# Mainboard_MCU_Breakout.net
KiCad netlist of a schematic drawn in Altium Designer
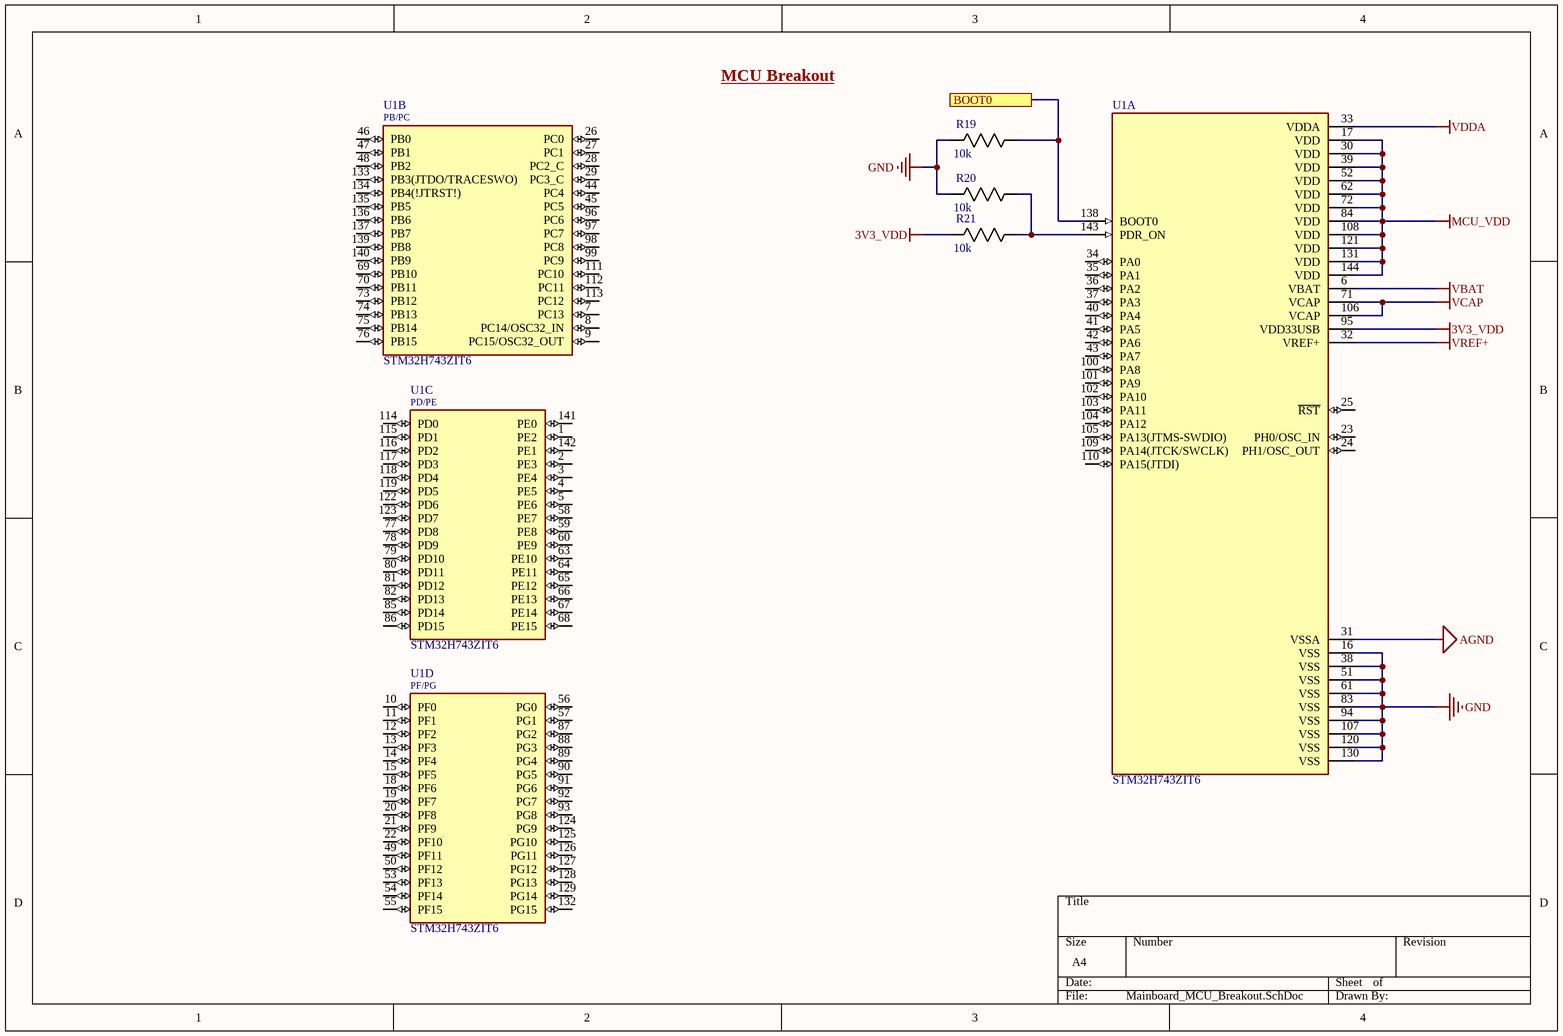
[diagram p0: Mainboard_MCU_Breakout.SchDoc]

(export (version "E")
  (design (tool "Eeschema 10.0.6"))
  (components
    (comp (ref "R19")
      (value "10k")
      (footprint "0805")
      (description "RES SMD 10K OHM 1% 1/8W 0805")
      (fields (field (name "TOLERANCE") "1%"))
      (libsource (lib "AltiumLibraries") (part "RES 10k 1/8W - 1%"))
    )
    (comp (ref "R20")
      (value "10k")
      (footprint "0805")
      (description "RES SMD 10K OHM 1% 1/8W 0805")
      (fields (field (name "TOLERANCE") "1%"))
      (libsource (lib "") (part "RES 10k 1/8W - 1%_1"))
    )
    (comp (ref "R21")
      (value "10k")
      (footprint "0805")
      (description "RES SMD 10K OHM 1% 1/8W 0805")
      (fields (field (name "TOLERANCE") "1%"))
      (libsource (lib "") (part "RES 10k 1/8W - 1%_1"))
    )
    (comp (ref "U1")
      (value "STM32H743ZIT6")
      (footprint "QFP50P2200X2200X160-144N")
      (description "ARM® Cortex®-M7 STM32H7 Microcontroller IC 32-Bit 480MHz 2MB (2M x 8) FLASH 144-LQFP (20x20)")
      (fields (field (name "MF") "STMicroelectronics"))
      (libsource (lib "AltiumLibraries") (part "STM32H743ZIT6"))
    )
  )
  (nets
    (net (code "1") (name "/BOOT0") (class "Default")
      (node (ref "R19") (pin "1") (pinfunction "R1_1") (pintype "passive"))
      (node (ref "U1") (pin "138") (pinfunction "BOOT0_138") (pintype "input"))
    )
    (net (code "2") (name "3V3_VDD") (class "Default")
      (node (ref "R21") (pin "2") (pinfunction "R2_2") (pintype "passive"))
      (node (ref "U1") (pin "95") (pinfunction "VDD33USB_95") (pintype "power_in"))
    )
    (net (code "3") (name "AGND") (class "Default")
      (node (ref "U1") (pin "31") (pinfunction "VSSA_31") (pintype "power_in"))
    )
    (net (code "4") (name "GND") (class "Default")
      (node (ref "R19") (pin "2") (pinfunction "R2_2") (pintype "passive"))
      (node (ref "R20") (pin "2") (pinfunction "R2_2") (pintype "passive"))
      (node (ref "U1") (pin "107") (pinfunction "VSS_107") (pintype "power_in"))
      (node (ref "U1") (pin "120") (pinfunction "VSS_120") (pintype "power_in"))
      (node (ref "U1") (pin "130") (pinfunction "VSS_130") (pintype "power_in"))
      (node (ref "U1") (pin "16") (pinfunction "VSS_16") (pintype "power_in"))
      (node (ref "U1") (pin "38") (pinfunction "VSS_38") (pintype "power_in"))
      (node (ref "U1") (pin "51") (pinfunction "VSS_51") (pintype "power_in"))
      (node (ref "U1") (pin "61") (pinfunction "VSS_61") (pintype "power_in"))
      (node (ref "U1") (pin "83") (pinfunction "VSS_83") (pintype "power_in"))
      (node (ref "U1") (pin "94") (pinfunction "VSS_94") (pintype "power_in"))
    )
    (net (code "5") (name "MCU_VDD") (class "Default")
      (node (ref "U1") (pin "108") (pinfunction "VDD_108") (pintype "power_in"))
      (node (ref "U1") (pin "121") (pinfunction "VDD_121") (pintype "power_in"))
      (node (ref "U1") (pin "131") (pinfunction "VDD_131") (pintype "power_in"))
      (node (ref "U1") (pin "144") (pinfunction "VDD_144") (pintype "power_in"))
      (node (ref "U1") (pin "17") (pinfunction "VDD_17") (pintype "power_in"))
      (node (ref "U1") (pin "30") (pinfunction "VDD_30") (pintype "power_in"))
      (node (ref "U1") (pin "39") (pinfunction "VDD_39") (pintype "power_in"))
      (node (ref "U1") (pin "52") (pinfunction "VDD_52") (pintype "power_in"))
      (node (ref "U1") (pin "62") (pinfunction "VDD_62") (pintype "power_in"))
      (node (ref "U1") (pin "72") (pinfunction "VDD_72") (pintype "power_in"))
      (node (ref "U1") (pin "84") (pinfunction "VDD_84") (pintype "power_in"))
    )
    (net (code "6") (name "Net-(R20-R1)") (class "Default")
      (node (ref "R20") (pin "1") (pinfunction "R1_1") (pintype "passive"))
      (node (ref "R21") (pin "1") (pinfunction "R1_1") (pintype "passive"))
      (node (ref "U1") (pin "143") (pinfunction "PDR_ON_143") (pintype "input"))
    )
    (net (code "7") (name "VBAT") (class "Default")
      (node (ref "U1") (pin "6") (pinfunction "VBAT_6") (pintype "power_in"))
    )
    (net (code "8") (name "VCAP") (class "Default")
      (node (ref "U1") (pin "106") (pinfunction "VCAP_106") (pintype "power_in"))
      (node (ref "U1") (pin "71") (pinfunction "VCAP_71") (pintype "power_in"))
    )
    (net (code "9") (name "VDDA") (class "Default")
      (node (ref "U1") (pin "33") (pinfunction "VDDA_33") (pintype "power_in"))
    )
    (net (code "10") (name "VREF+") (class "Default")
      (node (ref "U1") (pin "32") (pinfunction "VREF+_32") (pintype "power_in"))
    )
    (net (code "11") (name "unconnected-(U1A-PA0-Pad34)") (class "Default")
      (node (ref "U1") (pin "34") (pinfunction "PA0_34") (pintype "bidirectional"))
    )
    (net (code "12") (name "unconnected-(U1A-PA1-Pad35)") (class "Default")
      (node (ref "U1") (pin "35") (pinfunction "PA1_35") (pintype "bidirectional"))
    )
    (net (code "13") (name "unconnected-(U1A-PA2-Pad36)") (class "Default")
      (node (ref "U1") (pin "36") (pinfunction "PA2_36") (pintype "bidirectional"))
    )
    (net (code "14") (name "unconnected-(U1A-PA3-Pad37)") (class "Default")
      (node (ref "U1") (pin "37") (pinfunction "PA3_37") (pintype "bidirectional"))
    )
    (net (code "15") (name "unconnected-(U1A-PA4-Pad40)") (class "Default")
      (node (ref "U1") (pin "40") (pinfunction "PA4_40") (pintype "bidirectional"))
    )
    (net (code "16") (name "unconnected-(U1A-PA5-Pad41)") (class "Default")
      (node (ref "U1") (pin "41") (pinfunction "PA5_41") (pintype "bidirectional"))
    )
    (net (code "17") (name "unconnected-(U1A-PA6-Pad42)") (class "Default")
      (node (ref "U1") (pin "42") (pinfunction "PA6_42") (pintype "bidirectional"))
    )
    (net (code "18") (name "unconnected-(U1A-PA7-Pad43)") (class "Default")
      (node (ref "U1") (pin "43") (pinfunction "PA7_43") (pintype "bidirectional"))
    )
    (net (code "19") (name "unconnected-(U1A-PA8-Pad100)") (class "Default")
      (node (ref "U1") (pin "100") (pinfunction "PA8_100") (pintype "bidirectional"))
    )
    (net (code "20") (name "unconnected-(U1A-PA9-Pad101)") (class "Default")
      (node (ref "U1") (pin "101") (pinfunction "PA9_101") (pintype "bidirectional"))
    )
    (net (code "21") (name "unconnected-(U1A-PA10-Pad102)") (class "Default")
      (node (ref "U1") (pin "102") (pinfunction "PA10_102") (pintype "bidirectional"))
    )
    (net (code "22") (name "unconnected-(U1A-PA11-Pad103)") (class "Default")
      (node (ref "U1") (pin "103") (pinfunction "PA11_103") (pintype "bidirectional"))
    )
    (net (code "23") (name "unconnected-(U1A-PA12-Pad104)") (class "Default")
      (node (ref "U1") (pin "104") (pinfunction "PA12_104") (pintype "bidirectional"))
    )
    (net (code "24") (name "unconnected-(U1A-PA13(JTMS-SWDIO)-Pad105)") (class "Default")
      (node (ref "U1") (pin "105") (pinfunction "PA13(JTMS-SWDIO)_105") (pintype "bidirectional"))
    )
    (net (code "25") (name "unconnected-(U1A-PA14(JTCK{slash}SWCLK)-Pad109)") (class "Default")
      (node (ref "U1") (pin "109") (pinfunction "PA14(JTCK/SWCLK)_109") (pintype "bidirectional"))
    )
    (net (code "26") (name "unconnected-(U1A-PA15(JTDI)-Pad110)") (class "Default")
      (node (ref "U1") (pin "110") (pinfunction "PA15(JTDI)_110") (pintype "bidirectional"))
    )
    (net (code "27") (name "unconnected-(U1A-PH0{slash}OSC_IN-Pad23)") (class "Default")
      (node (ref "U1") (pin "23") (pinfunction "PH0/OSC_IN_23") (pintype "bidirectional"))
    )
    (net (code "28") (name "unconnected-(U1A-PH1{slash}OSC_OUT-Pad24)") (class "Default")
      (node (ref "U1") (pin "24") (pinfunction "PH1/OSC_OUT_24") (pintype "bidirectional"))
    )
    (net (code "29") (name "unconnected-(U1A-~{RST}-Pad25)") (class "Default")
      (node (ref "U1") (pin "25") (pinfunction "~{RST}_25") (pintype "bidirectional"))
    )
    (net (code "30") (name "unconnected-(U1B-PB0-Pad46)") (class "Default")
      (node (ref "U1") (pin "46") (pinfunction "PB0_46") (pintype "bidirectional"))
    )
    (net (code "31") (name "unconnected-(U1B-PB1-Pad47)") (class "Default")
      (node (ref "U1") (pin "47") (pinfunction "PB1_47") (pintype "bidirectional"))
    )
    (net (code "32") (name "unconnected-(U1B-PB2-Pad48)") (class "Default")
      (node (ref "U1") (pin "48") (pinfunction "PB2_48") (pintype "bidirectional"))
    )
    (net (code "33") (name "unconnected-(U1B-PB3(JTDO{slash}TRACESWO)-Pad133)") (class "Default")
      (node (ref "U1") (pin "133") (pinfunction "PB3(JTDO/TRACESWO)_133") (pintype "bidirectional"))
    )
    (net (code "34") (name "unconnected-(U1B-PB4(!JTRST!)-Pad134)") (class "Default")
      (node (ref "U1") (pin "134") (pinfunction "PB4(!JTRST!)_134") (pintype "bidirectional"))
    )
    (net (code "35") (name "unconnected-(U1B-PB5-Pad135)") (class "Default")
      (node (ref "U1") (pin "135") (pinfunction "PB5_135") (pintype "bidirectional"))
    )
    (net (code "36") (name "unconnected-(U1B-PB6-Pad136)") (class "Default")
      (node (ref "U1") (pin "136") (pinfunction "PB6_136") (pintype "bidirectional"))
    )
    (net (code "37") (name "unconnected-(U1B-PB7-Pad137)") (class "Default")
      (node (ref "U1") (pin "137") (pinfunction "PB7_137") (pintype "bidirectional"))
    )
    (net (code "38") (name "unconnected-(U1B-PB8-Pad139)") (class "Default")
      (node (ref "U1") (pin "139") (pinfunction "PB8_139") (pintype "bidirectional"))
    )
    (net (code "39") (name "unconnected-(U1B-PB9-Pad140)") (class "Default")
      (node (ref "U1") (pin "140") (pinfunction "PB9_140") (pintype "bidirectional"))
    )
    (net (code "40") (name "unconnected-(U1B-PB10-Pad69)") (class "Default")
      (node (ref "U1") (pin "69") (pinfunction "PB10_69") (pintype "bidirectional"))
    )
    (net (code "41") (name "unconnected-(U1B-PB11-Pad70)") (class "Default")
      (node (ref "U1") (pin "70") (pinfunction "PB11_70") (pintype "bidirectional"))
    )
    (net (code "42") (name "unconnected-(U1B-PB12-Pad73)") (class "Default")
      (node (ref "U1") (pin "73") (pinfunction "PB12_73") (pintype "bidirectional"))
    )
    (net (code "43") (name "unconnected-(U1B-PB13-Pad74)") (class "Default")
      (node (ref "U1") (pin "74") (pinfunction "PB13_74") (pintype "bidirectional"))
    )
    (net (code "44") (name "unconnected-(U1B-PB14-Pad75)") (class "Default")
      (node (ref "U1") (pin "75") (pinfunction "PB14_75") (pintype "bidirectional"))
    )
    (net (code "45") (name "unconnected-(U1B-PB15-Pad76)") (class "Default")
      (node (ref "U1") (pin "76") (pinfunction "PB15_76") (pintype "bidirectional"))
    )
    (net (code "46") (name "unconnected-(U1B-PC0-Pad26)") (class "Default")
      (node (ref "U1") (pin "26") (pinfunction "PC0_26") (pintype "bidirectional"))
    )
    (net (code "47") (name "unconnected-(U1B-PC1-Pad27)") (class "Default")
      (node (ref "U1") (pin "27") (pinfunction "PC1_27") (pintype "bidirectional"))
    )
    (net (code "48") (name "unconnected-(U1B-PC2_C-Pad28)") (class "Default")
      (node (ref "U1") (pin "28") (pinfunction "PC2_C_28") (pintype "bidirectional"))
    )
    (net (code "49") (name "unconnected-(U1B-PC3_C-Pad29)") (class "Default")
      (node (ref "U1") (pin "29") (pinfunction "PC3_C_29") (pintype "bidirectional"))
    )
    (net (code "50") (name "unconnected-(U1B-PC4-Pad44)") (class "Default")
      (node (ref "U1") (pin "44") (pinfunction "PC4_44") (pintype "bidirectional"))
    )
    (net (code "51") (name "unconnected-(U1B-PC5-Pad45)") (class "Default")
      (node (ref "U1") (pin "45") (pinfunction "PC5_45") (pintype "bidirectional"))
    )
    (net (code "52") (name "unconnected-(U1B-PC6-Pad96)") (class "Default")
      (node (ref "U1") (pin "96") (pinfunction "PC6_96") (pintype "bidirectional"))
    )
    (net (code "53") (name "unconnected-(U1B-PC7-Pad97)") (class "Default")
      (node (ref "U1") (pin "97") (pinfunction "PC7_97") (pintype "bidirectional"))
    )
    (net (code "54") (name "unconnected-(U1B-PC8-Pad98)") (class "Default")
      (node (ref "U1") (pin "98") (pinfunction "PC8_98") (pintype "bidirectional"))
    )
    (net (code "55") (name "unconnected-(U1B-PC9-Pad99)") (class "Default")
      (node (ref "U1") (pin "99") (pinfunction "PC9_99") (pintype "bidirectional"))
    )
    (net (code "56") (name "unconnected-(U1B-PC10-Pad111)") (class "Default")
      (node (ref "U1") (pin "111") (pinfunction "PC10_111") (pintype "bidirectional"))
    )
    (net (code "57") (name "unconnected-(U1B-PC11-Pad112)") (class "Default")
      (node (ref "U1") (pin "112") (pinfunction "PC11_112") (pintype "bidirectional"))
    )
    (net (code "58") (name "unconnected-(U1B-PC12-Pad113)") (class "Default")
      (node (ref "U1") (pin "113") (pinfunction "PC12_113") (pintype "bidirectional"))
    )
    (net (code "59") (name "unconnected-(U1B-PC13-Pad7)") (class "Default")
      (node (ref "U1") (pin "7") (pinfunction "PC13_7") (pintype "bidirectional"))
    )
    (net (code "60") (name "unconnected-(U1B-PC14{slash}OSC32_IN-Pad8)") (class "Default")
      (node (ref "U1") (pin "8") (pinfunction "PC14/OSC32_IN_8") (pintype "bidirectional"))
    )
    (net (code "61") (name "unconnected-(U1B-PC15{slash}OSC32_OUT-Pad9)") (class "Default")
      (node (ref "U1") (pin "9") (pinfunction "PC15/OSC32_OUT_9") (pintype "bidirectional"))
    )
    (net (code "62") (name "unconnected-(U1C-PD0-Pad114)") (class "Default")
      (node (ref "U1") (pin "114") (pinfunction "PD0_114") (pintype "bidirectional"))
    )
    (net (code "63") (name "unconnected-(U1C-PD1-Pad115)") (class "Default")
      (node (ref "U1") (pin "115") (pinfunction "PD1_115") (pintype "bidirectional"))
    )
    (net (code "64") (name "unconnected-(U1C-PD2-Pad116)") (class "Default")
      (node (ref "U1") (pin "116") (pinfunction "PD2_116") (pintype "bidirectional"))
    )
    (net (code "65") (name "unconnected-(U1C-PD3-Pad117)") (class "Default")
      (node (ref "U1") (pin "117") (pinfunction "PD3_117") (pintype "bidirectional"))
    )
    (net (code "66") (name "unconnected-(U1C-PD4-Pad118)") (class "Default")
      (node (ref "U1") (pin "118") (pinfunction "PD4_118") (pintype "bidirectional"))
    )
    (net (code "67") (name "unconnected-(U1C-PD5-Pad119)") (class "Default")
      (node (ref "U1") (pin "119") (pinfunction "PD5_119") (pintype "bidirectional"))
    )
    (net (code "68") (name "unconnected-(U1C-PD6-Pad122)") (class "Default")
      (node (ref "U1") (pin "122") (pinfunction "PD6_122") (pintype "bidirectional"))
    )
    (net (code "69") (name "unconnected-(U1C-PD7-Pad123)") (class "Default")
      (node (ref "U1") (pin "123") (pinfunction "PD7_123") (pintype "bidirectional"))
    )
    (net (code "70") (name "unconnected-(U1C-PD8-Pad77)") (class "Default")
      (node (ref "U1") (pin "77") (pinfunction "PD8_77") (pintype "bidirectional"))
    )
    (net (code "71") (name "unconnected-(U1C-PD9-Pad78)") (class "Default")
      (node (ref "U1") (pin "78") (pinfunction "PD9_78") (pintype "bidirectional"))
    )
    (net (code "72") (name "unconnected-(U1C-PD10-Pad79)") (class "Default")
      (node (ref "U1") (pin "79") (pinfunction "PD10_79") (pintype "bidirectional"))
    )
    (net (code "73") (name "unconnected-(U1C-PD11-Pad80)") (class "Default")
      (node (ref "U1") (pin "80") (pinfunction "PD11_80") (pintype "bidirectional"))
    )
    (net (code "74") (name "unconnected-(U1C-PD12-Pad81)") (class "Default")
      (node (ref "U1") (pin "81") (pinfunction "PD12_81") (pintype "bidirectional"))
    )
    (net (code "75") (name "unconnected-(U1C-PD13-Pad82)") (class "Default")
      (node (ref "U1") (pin "82") (pinfunction "PD13_82") (pintype "bidirectional"))
    )
    (net (code "76") (name "unconnected-(U1C-PD14-Pad85)") (class "Default")
      (node (ref "U1") (pin "85") (pinfunction "PD14_85") (pintype "bidirectional"))
    )
    (net (code "77") (name "unconnected-(U1C-PD15-Pad86)") (class "Default")
      (node (ref "U1") (pin "86") (pinfunction "PD15_86") (pintype "bidirectional"))
    )
    (net (code "78") (name "unconnected-(U1C-PE0-Pad141)") (class "Default")
      (node (ref "U1") (pin "141") (pinfunction "PE0_141") (pintype "bidirectional"))
    )
    (net (code "79") (name "unconnected-(U1C-PE1-Pad142)") (class "Default")
      (node (ref "U1") (pin "142") (pinfunction "PE1_142") (pintype "bidirectional"))
    )
    (net (code "80") (name "unconnected-(U1C-PE2-Pad1)") (class "Default")
      (node (ref "U1") (pin "1") (pinfunction "PE2_1") (pintype "bidirectional"))
    )
    (net (code "81") (name "unconnected-(U1C-PE3-Pad2)") (class "Default")
      (node (ref "U1") (pin "2") (pinfunction "PE3_2") (pintype "bidirectional"))
    )
    (net (code "82") (name "unconnected-(U1C-PE4-Pad3)") (class "Default")
      (node (ref "U1") (pin "3") (pinfunction "PE4_3") (pintype "bidirectional"))
    )
    (net (code "83") (name "unconnected-(U1C-PE5-Pad4)") (class "Default")
      (node (ref "U1") (pin "4") (pinfunction "PE5_4") (pintype "bidirectional"))
    )
    (net (code "84") (name "unconnected-(U1C-PE6-Pad5)") (class "Default")
      (node (ref "U1") (pin "5") (pinfunction "PE6_5") (pintype "bidirectional"))
    )
    (net (code "85") (name "unconnected-(U1C-PE7-Pad58)") (class "Default")
      (node (ref "U1") (pin "58") (pinfunction "PE7_58") (pintype "bidirectional"))
    )
    (net (code "86") (name "unconnected-(U1C-PE8-Pad59)") (class "Default")
      (node (ref "U1") (pin "59") (pinfunction "PE8_59") (pintype "bidirectional"))
    )
    (net (code "87") (name "unconnected-(U1C-PE9-Pad60)") (class "Default")
      (node (ref "U1") (pin "60") (pinfunction "PE9_60") (pintype "bidirectional"))
    )
    (net (code "88") (name "unconnected-(U1C-PE10-Pad63)") (class "Default")
      (node (ref "U1") (pin "63") (pinfunction "PE10_63") (pintype "bidirectional"))
    )
    (net (code "89") (name "unconnected-(U1C-PE11-Pad64)") (class "Default")
      (node (ref "U1") (pin "64") (pinfunction "PE11_64") (pintype "bidirectional"))
    )
    (net (code "90") (name "unconnected-(U1C-PE12-Pad65)") (class "Default")
      (node (ref "U1") (pin "65") (pinfunction "PE12_65") (pintype "bidirectional"))
    )
    (net (code "91") (name "unconnected-(U1C-PE13-Pad66)") (class "Default")
      (node (ref "U1") (pin "66") (pinfunction "PE13_66") (pintype "bidirectional"))
    )
    (net (code "92") (name "unconnected-(U1C-PE14-Pad67)") (class "Default")
      (node (ref "U1") (pin "67") (pinfunction "PE14_67") (pintype "bidirectional"))
    )
    (net (code "93") (name "unconnected-(U1C-PE15-Pad68)") (class "Default")
      (node (ref "U1") (pin "68") (pinfunction "PE15_68") (pintype "bidirectional"))
    )
    (net (code "94") (name "unconnected-(U1D-PF0-Pad10)") (class "Default")
      (node (ref "U1") (pin "10") (pinfunction "PF0_10") (pintype "bidirectional"))
    )
    (net (code "95") (name "unconnected-(U1D-PF1-Pad11)") (class "Default")
      (node (ref "U1") (pin "11") (pinfunction "PF1_11") (pintype "bidirectional"))
    )
    (net (code "96") (name "unconnected-(U1D-PF2-Pad12)") (class "Default")
      (node (ref "U1") (pin "12") (pinfunction "PF2_12") (pintype "bidirectional"))
    )
    (net (code "97") (name "unconnected-(U1D-PF3-Pad13)") (class "Default")
      (node (ref "U1") (pin "13") (pinfunction "PF3_13") (pintype "bidirectional"))
    )
    (net (code "98") (name "unconnected-(U1D-PF4-Pad14)") (class "Default")
      (node (ref "U1") (pin "14") (pinfunction "PF4_14") (pintype "bidirectional"))
    )
    (net (code "99") (name "unconnected-(U1D-PF5-Pad15)") (class "Default")
      (node (ref "U1") (pin "15") (pinfunction "PF5_15") (pintype "bidirectional"))
    )
    (net (code "100") (name "unconnected-(U1D-PF6-Pad18)") (class "Default")
      (node (ref "U1") (pin "18") (pinfunction "PF6_18") (pintype "bidirectional"))
    )
    (net (code "101") (name "unconnected-(U1D-PF7-Pad19)") (class "Default")
      (node (ref "U1") (pin "19") (pinfunction "PF7_19") (pintype "bidirectional"))
    )
    (net (code "102") (name "unconnected-(U1D-PF8-Pad20)") (class "Default")
      (node (ref "U1") (pin "20") (pinfunction "PF8_20") (pintype "bidirectional"))
    )
    (net (code "103") (name "unconnected-(U1D-PF9-Pad21)") (class "Default")
      (node (ref "U1") (pin "21") (pinfunction "PF9_21") (pintype "bidirectional"))
    )
    (net (code "104") (name "unconnected-(U1D-PF10-Pad22)") (class "Default")
      (node (ref "U1") (pin "22") (pinfunction "PF10_22") (pintype "bidirectional"))
    )
    (net (code "105") (name "unconnected-(U1D-PF11-Pad49)") (class "Default")
      (node (ref "U1") (pin "49") (pinfunction "PF11_49") (pintype "bidirectional"))
    )
    (net (code "106") (name "unconnected-(U1D-PF12-Pad50)") (class "Default")
      (node (ref "U1") (pin "50") (pinfunction "PF12_50") (pintype "bidirectional"))
    )
    (net (code "107") (name "unconnected-(U1D-PF13-Pad53)") (class "Default")
      (node (ref "U1") (pin "53") (pinfunction "PF13_53") (pintype "bidirectional"))
    )
    (net (code "108") (name "unconnected-(U1D-PF14-Pad54)") (class "Default")
      (node (ref "U1") (pin "54") (pinfunction "PF14_54") (pintype "bidirectional"))
    )
    (net (code "109") (name "unconnected-(U1D-PF15-Pad55)") (class "Default")
      (node (ref "U1") (pin "55") (pinfunction "PF15_55") (pintype "bidirectional"))
    )
    (net (code "110") (name "unconnected-(U1D-PG0-Pad56)") (class "Default")
      (node (ref "U1") (pin "56") (pinfunction "PG0_56") (pintype "bidirectional"))
    )
    (net (code "111") (name "unconnected-(U1D-PG1-Pad57)") (class "Default")
      (node (ref "U1") (pin "57") (pinfunction "PG1_57") (pintype "bidirectional"))
    )
    (net (code "112") (name "unconnected-(U1D-PG2-Pad87)") (class "Default")
      (node (ref "U1") (pin "87") (pinfunction "PG2_87") (pintype "bidirectional"))
    )
    (net (code "113") (name "unconnected-(U1D-PG3-Pad88)") (class "Default")
      (node (ref "U1") (pin "88") (pinfunction "PG3_88") (pintype "bidirectional"))
    )
    (net (code "114") (name "unconnected-(U1D-PG4-Pad89)") (class "Default")
      (node (ref "U1") (pin "89") (pinfunction "PG4_89") (pintype "bidirectional"))
    )
    (net (code "115") (name "unconnected-(U1D-PG5-Pad90)") (class "Default")
      (node (ref "U1") (pin "90") (pinfunction "PG5_90") (pintype "bidirectional"))
    )
    (net (code "116") (name "unconnected-(U1D-PG6-Pad91)") (class "Default")
      (node (ref "U1") (pin "91") (pinfunction "PG6_91") (pintype "bidirectional"))
    )
    (net (code "117") (name "unconnected-(U1D-PG7-Pad92)") (class "Default")
      (node (ref "U1") (pin "92") (pinfunction "PG7_92") (pintype "bidirectional"))
    )
    (net (code "118") (name "unconnected-(U1D-PG8-Pad93)") (class "Default")
      (node (ref "U1") (pin "93") (pinfunction "PG8_93") (pintype "bidirectional"))
    )
    (net (code "119") (name "unconnected-(U1D-PG9-Pad124)") (class "Default")
      (node (ref "U1") (pin "124") (pinfunction "PG9_124") (pintype "bidirectional"))
    )
    (net (code "120") (name "unconnected-(U1D-PG10-Pad125)") (class "Default")
      (node (ref "U1") (pin "125") (pinfunction "PG10_125") (pintype "bidirectional"))
    )
    (net (code "121") (name "unconnected-(U1D-PG11-Pad126)") (class "Default")
      (node (ref "U1") (pin "126") (pinfunction "PG11_126") (pintype "bidirectional"))
    )
    (net (code "122") (name "unconnected-(U1D-PG12-Pad127)") (class "Default")
      (node (ref "U1") (pin "127") (pinfunction "PG12_127") (pintype "bidirectional"))
    )
    (net (code "123") (name "unconnected-(U1D-PG13-Pad128)") (class "Default")
      (node (ref "U1") (pin "128") (pinfunction "PG13_128") (pintype "bidirectional"))
    )
    (net (code "124") (name "unconnected-(U1D-PG14-Pad129)") (class "Default")
      (node (ref "U1") (pin "129") (pinfunction "PG14_129") (pintype "bidirectional"))
    )
    (net (code "125") (name "unconnected-(U1D-PG15-Pad132)") (class "Default")
      (node (ref "U1") (pin "132") (pinfunction "PG15_132") (pintype "bidirectional"))
    )
  )
)
